# PGTN020_envelope4.net
KiCad netlist of a schematic drawn in EAGLE
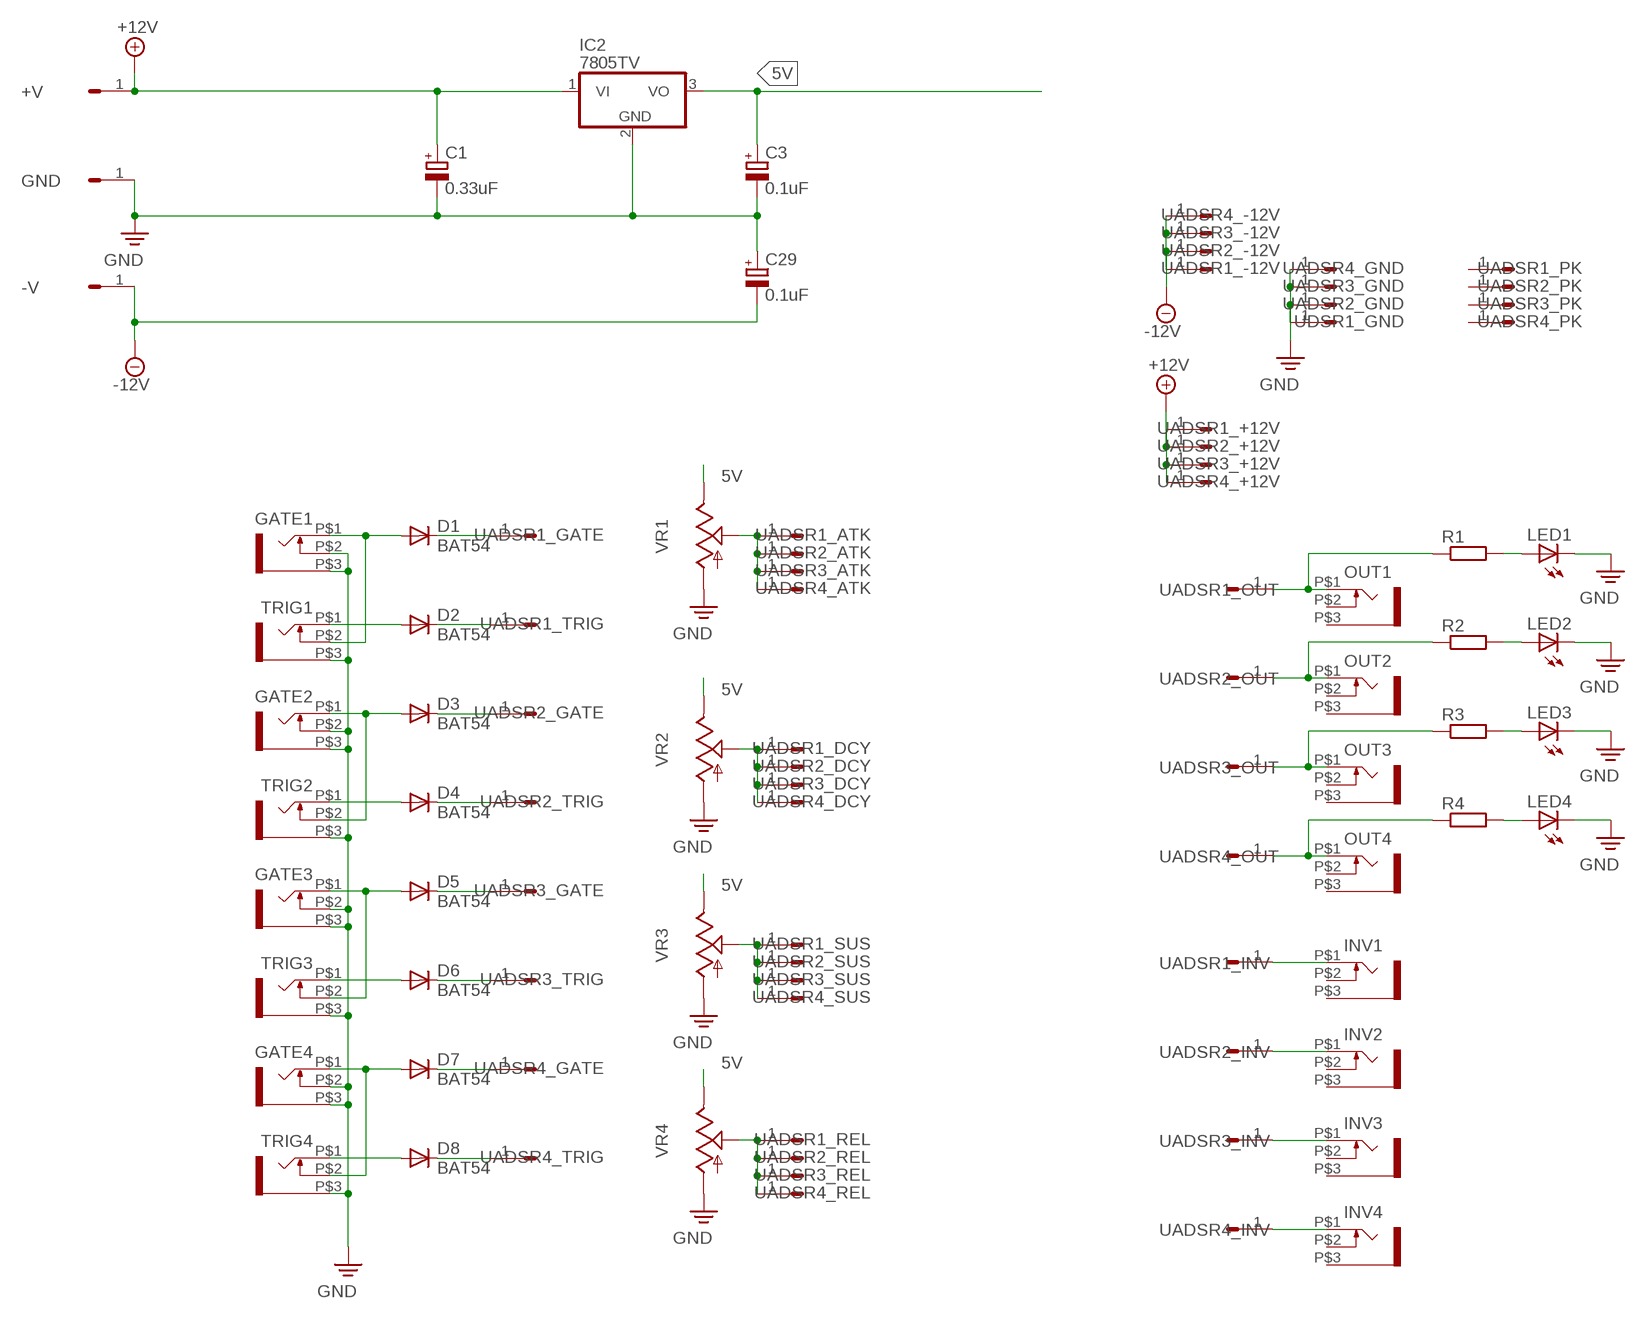
[diagram p0: schematic, sheet 1]

(export (version "E")
  (design (tool "Eeschema 10.0.6"))
  (components
    (comp (ref "+V")
      (value "HEADER/MALE/01")
      (footprint "eagle-import:HEADER_MALE_01")
      (fields (field (name "SPICEPREFIX") "X"))
      (libsource (lib "eagle-import") (part "HEADER/MALE/01"))
    )
    (comp (ref "-V")
      (value "HEADER/MALE/01")
      (footprint "eagle-import:HEADER_MALE_01")
      (fields (field (name "SPICEPREFIX") "X"))
      (libsource (lib "eagle-import") (part "HEADER/MALE/01"))
    )
    (comp (ref "C1")
      (value "0.33uF")
      (footprint "eagle-import:E2,5-6")
      (fields (field (name "SPICEPREFIX") "C"))
      (libsource (lib "eagle-import") (part "CAPACITOR/POLARIZEDE2.5-6"))
    )
    (comp (ref "C3")
      (value "0.1uF")
      (footprint "eagle-import:E2,5-6")
      (fields (field (name "SPICEPREFIX") "C"))
      (libsource (lib "eagle-import") (part "CAPACITOR/POLARIZEDE2.5-6"))
    )
    (comp (ref "C29")
      (value "0.1uF")
      (footprint "eagle-import:E2,5-6")
      (fields (field (name "SPICEPREFIX") "C"))
      (libsource (lib "eagle-import") (part "CAPACITOR/POLARIZEDE2.5-6"))
    )
    (comp (ref "D1")
      (value "BAT54")
      (footprint "eagle-import:DO35-7")
      (libsource (lib "eagle-import") (part "1N4148DO35-7"))
    )
    (comp (ref "D2")
      (value "BAT54")
      (footprint "eagle-import:DO35-7")
      (libsource (lib "eagle-import") (part "1N4148DO35-7"))
    )
    (comp (ref "D3")
      (value "BAT54")
      (footprint "eagle-import:DO35-7")
      (libsource (lib "eagle-import") (part "1N4148DO35-7"))
    )
    (comp (ref "D4")
      (value "BAT54")
      (footprint "eagle-import:DO35-7")
      (libsource (lib "eagle-import") (part "1N4148DO35-7"))
    )
    (comp (ref "D5")
      (value "BAT54")
      (footprint "eagle-import:DO35-7")
      (libsource (lib "eagle-import") (part "1N4148DO35-7"))
    )
    (comp (ref "D6")
      (value "BAT54")
      (footprint "eagle-import:DO35-7")
      (libsource (lib "eagle-import") (part "1N4148DO35-7"))
    )
    (comp (ref "D7")
      (value "BAT54")
      (footprint "eagle-import:DO35-7")
      (libsource (lib "eagle-import") (part "1N4148DO35-7"))
    )
    (comp (ref "D8")
      (value "BAT54")
      (footprint "eagle-import:DO35-7")
      (libsource (lib "eagle-import") (part "1N4148DO35-7"))
    )
    (comp (ref "GATE1")
      (value "WQP-PJ301M-12_JACK")
      (footprint "eagle-import:WQP-PJ301M-12_JACK")
      (libsource (lib "eagle-import") (part "WQP-PJ301M-12_JACK"))
    )
    (comp (ref "GATE2")
      (value "WQP-PJ301M-12_JACK")
      (footprint "eagle-import:WQP-PJ301M-12_JACK")
      (libsource (lib "eagle-import") (part "WQP-PJ301M-12_JACK"))
    )
    (comp (ref "GATE3")
      (value "WQP-PJ301M-12_JACK")
      (footprint "eagle-import:WQP-PJ301M-12_JACK")
      (libsource (lib "eagle-import") (part "WQP-PJ301M-12_JACK"))
    )
    (comp (ref "GATE4")
      (value "WQP-PJ301M-12_JACK")
      (footprint "eagle-import:WQP-PJ301M-12_JACK")
      (libsource (lib "eagle-import") (part "WQP-PJ301M-12_JACK"))
    )
    (comp (ref "GND")
      (value "HEADER/MALE/01")
      (footprint "eagle-import:HEADER_MALE_01")
      (fields (field (name "SPICEPREFIX") "X"))
      (libsource (lib "eagle-import") (part "HEADER/MALE/01"))
    )
    (comp (ref "IC2")
      (value "7805TV")
      (footprint "eagle-import:TO220V")
      (libsource (lib "eagle-import") (part "78TV05"))
    )
    (comp (ref "INV1")
      (value "WQP-PJ301M-12_JACK")
      (footprint "eagle-import:WQP-PJ301M-12_JACK")
      (libsource (lib "eagle-import") (part "WQP-PJ301M-12_JACK"))
    )
    (comp (ref "INV2")
      (value "WQP-PJ301M-12_JACK")
      (footprint "eagle-import:WQP-PJ301M-12_JACK")
      (libsource (lib "eagle-import") (part "WQP-PJ301M-12_JACK"))
    )
    (comp (ref "INV3")
      (value "WQP-PJ301M-12_JACK")
      (footprint "eagle-import:WQP-PJ301M-12_JACK")
      (libsource (lib "eagle-import") (part "WQP-PJ301M-12_JACK"))
    )
    (comp (ref "INV4")
      (value "WQP-PJ301M-12_JACK")
      (footprint "eagle-import:WQP-PJ301M-12_JACK")
      (libsource (lib "eagle-import") (part "WQP-PJ301M-12_JACK"))
    )
    (comp (ref "LED1")
      (value "LED5MM")
      (footprint "eagle-import:LED5MM")
      (libsource (lib "eagle-import") (part "LED5MM"))
    )
    (comp (ref "LED2")
      (value "LED5MM")
      (footprint "eagle-import:LED5MM")
      (libsource (lib "eagle-import") (part "LED5MM"))
    )
    (comp (ref "LED3")
      (value "LED5MM")
      (footprint "eagle-import:LED5MM")
      (libsource (lib "eagle-import") (part "LED5MM"))
    )
    (comp (ref "LED4")
      (value "LED5MM")
      (footprint "eagle-import:LED5MM")
      (libsource (lib "eagle-import") (part "LED5MM"))
    )
    (comp (ref "OUT1")
      (value "WQP-PJ301M-12_JACK")
      (footprint "eagle-import:WQP-PJ301M-12_JACK")
      (libsource (lib "eagle-import") (part "WQP-PJ301M-12_JACK"))
    )
    (comp (ref "OUT2")
      (value "WQP-PJ301M-12_JACK")
      (footprint "eagle-import:WQP-PJ301M-12_JACK")
      (libsource (lib "eagle-import") (part "WQP-PJ301M-12_JACK"))
    )
    (comp (ref "OUT3")
      (value "WQP-PJ301M-12_JACK")
      (footprint "eagle-import:WQP-PJ301M-12_JACK")
      (libsource (lib "eagle-import") (part "WQP-PJ301M-12_JACK"))
    )
    (comp (ref "OUT4")
      (value "WQP-PJ301M-12_JACK")
      (footprint "eagle-import:WQP-PJ301M-12_JACK")
      (libsource (lib "eagle-import") (part "WQP-PJ301M-12_JACK"))
    )
    (comp (ref "R1")
      (value "RESISTORRESISTOR/UPRIGHT/7.5")
      (footprint "eagle-import:RESISTOR_7.5")
      (libsource (lib "eagle-import") (part "RESISTORRESISTOR/UPRIGHT/7.5"))
    )
    (comp (ref "R2")
      (value "RESISTORRESISTOR/UPRIGHT/7.5")
      (footprint "eagle-import:RESISTOR_7.5")
      (libsource (lib "eagle-import") (part "RESISTORRESISTOR/UPRIGHT/7.5"))
    )
    (comp (ref "R3")
      (value "RESISTORRESISTOR/UPRIGHT/7.5")
      (footprint "eagle-import:RESISTOR_7.5")
      (libsource (lib "eagle-import") (part "RESISTORRESISTOR/UPRIGHT/7.5"))
    )
    (comp (ref "R4")
      (value "RESISTORRESISTOR/UPRIGHT/7.5")
      (footprint "eagle-import:RESISTOR_7.5")
      (libsource (lib "eagle-import") (part "RESISTORRESISTOR/UPRIGHT/7.5"))
    )
    (comp (ref "TRIG1")
      (value "WQP-PJ301M-12_JACK")
      (footprint "eagle-import:WQP-PJ301M-12_JACK")
      (libsource (lib "eagle-import") (part "WQP-PJ301M-12_JACK"))
    )
    (comp (ref "TRIG2")
      (value "WQP-PJ301M-12_JACK")
      (footprint "eagle-import:WQP-PJ301M-12_JACK")
      (libsource (lib "eagle-import") (part "WQP-PJ301M-12_JACK"))
    )
    (comp (ref "TRIG3")
      (value "WQP-PJ301M-12_JACK")
      (footprint "eagle-import:WQP-PJ301M-12_JACK")
      (libsource (lib "eagle-import") (part "WQP-PJ301M-12_JACK"))
    )
    (comp (ref "TRIG4")
      (value "WQP-PJ301M-12_JACK")
      (footprint "eagle-import:WQP-PJ301M-12_JACK")
      (libsource (lib "eagle-import") (part "WQP-PJ301M-12_JACK"))
    )
    (comp (ref "UADSR1_+12V")
      (value "HEADER/MALE/01")
      (footprint "eagle-import:HEADER_MALE_01")
      (fields (field (name "SPICEPREFIX") "X"))
      (libsource (lib "eagle-import") (part "HEADER/MALE/01"))
    )
    (comp (ref "UADSR1_-12V")
      (value "HEADER/MALE/01")
      (footprint "eagle-import:HEADER_MALE_01")
      (fields (field (name "SPICEPREFIX") "X"))
      (libsource (lib "eagle-import") (part "HEADER/MALE/01"))
    )
    (comp (ref "UADSR1_ATK")
      (value "HEADER/MALE/01")
      (footprint "eagle-import:HEADER_MALE_01")
      (fields (field (name "SPICEPREFIX") "X"))
      (libsource (lib "eagle-import") (part "HEADER/MALE/01"))
    )
    (comp (ref "UADSR1_DCY")
      (value "HEADER/MALE/01")
      (footprint "eagle-import:HEADER_MALE_01")
      (fields (field (name "SPICEPREFIX") "X"))
      (libsource (lib "eagle-import") (part "HEADER/MALE/01"))
    )
    (comp (ref "UADSR1_GATE")
      (value "HEADER/MALE/01")
      (footprint "eagle-import:HEADER_MALE_01")
      (fields (field (name "SPICEPREFIX") "X"))
      (libsource (lib "eagle-import") (part "HEADER/MALE/01"))
    )
    (comp (ref "UADSR1_INV")
      (value "HEADER/MALE/01")
      (footprint "eagle-import:HEADER_MALE_01")
      (fields (field (name "SPICEPREFIX") "X"))
      (libsource (lib "eagle-import") (part "HEADER/MALE/01"))
    )
    (comp (ref "UADSR1_OUT")
      (value "HEADER/MALE/01")
      (footprint "eagle-import:HEADER_MALE_01")
      (fields (field (name "SPICEPREFIX") "X"))
      (libsource (lib "eagle-import") (part "HEADER/MALE/01"))
    )
    (comp (ref "UADSR1_PK")
      (value "HEADER/MALE/01")
      (footprint "eagle-import:HEADER_MALE_01")
      (fields (field (name "SPICEPREFIX") "X"))
      (libsource (lib "eagle-import") (part "HEADER/MALE/01"))
    )
    (comp (ref "UADSR1_REL")
      (value "HEADER/MALE/01")
      (footprint "eagle-import:HEADER_MALE_01")
      (fields (field (name "SPICEPREFIX") "X"))
      (libsource (lib "eagle-import") (part "HEADER/MALE/01"))
    )
    (comp (ref "UADSR1_SUS")
      (value "HEADER/MALE/01")
      (footprint "eagle-import:HEADER_MALE_01")
      (fields (field (name "SPICEPREFIX") "X"))
      (libsource (lib "eagle-import") (part "HEADER/MALE/01"))
    )
    (comp (ref "UADSR1_TRIG")
      (value "HEADER/MALE/01")
      (footprint "eagle-import:HEADER_MALE_01")
      (fields (field (name "SPICEPREFIX") "X"))
      (libsource (lib "eagle-import") (part "HEADER/MALE/01"))
    )
    (comp (ref "UADSR2_+12V")
      (value "HEADER/MALE/01")
      (footprint "eagle-import:HEADER_MALE_01")
      (fields (field (name "SPICEPREFIX") "X"))
      (libsource (lib "eagle-import") (part "HEADER/MALE/01"))
    )
    (comp (ref "UADSR2_-12V")
      (value "HEADER/MALE/01")
      (footprint "eagle-import:HEADER_MALE_01")
      (fields (field (name "SPICEPREFIX") "X"))
      (libsource (lib "eagle-import") (part "HEADER/MALE/01"))
    )
    (comp (ref "UADSR2_ATK")
      (value "HEADER/MALE/01")
      (footprint "eagle-import:HEADER_MALE_01")
      (fields (field (name "SPICEPREFIX") "X"))
      (libsource (lib "eagle-import") (part "HEADER/MALE/01"))
    )
    (comp (ref "UADSR2_DCY")
      (value "HEADER/MALE/01")
      (footprint "eagle-import:HEADER_MALE_01")
      (fields (field (name "SPICEPREFIX") "X"))
      (libsource (lib "eagle-import") (part "HEADER/MALE/01"))
    )
    (comp (ref "UADSR2_GATE")
      (value "HEADER/MALE/01")
      (footprint "eagle-import:HEADER_MALE_01")
      (fields (field (name "SPICEPREFIX") "X"))
      (libsource (lib "eagle-import") (part "HEADER/MALE/01"))
    )
    (comp (ref "UADSR2_GND")
      (value "HEADER/MALE/01")
      (footprint "eagle-import:HEADER_MALE_01")
      (fields (field (name "SPICEPREFIX") "X"))
      (libsource (lib "eagle-import") (part "HEADER/MALE/01"))
    )
    (comp (ref "UADSR2_INV")
      (value "HEADER/MALE/01")
      (footprint "eagle-import:HEADER_MALE_01")
      (fields (field (name "SPICEPREFIX") "X"))
      (libsource (lib "eagle-import") (part "HEADER/MALE/01"))
    )
    (comp (ref "UADSR2_OUT")
      (value "HEADER/MALE/01")
      (footprint "eagle-import:HEADER_MALE_01")
      (fields (field (name "SPICEPREFIX") "X"))
      (libsource (lib "eagle-import") (part "HEADER/MALE/01"))
    )
    (comp (ref "UADSR2_PK")
      (value "HEADER/MALE/01")
      (footprint "eagle-import:HEADER_MALE_01")
      (fields (field (name "SPICEPREFIX") "X"))
      (libsource (lib "eagle-import") (part "HEADER/MALE/01"))
    )
    (comp (ref "UADSR2_REL")
      (value "HEADER/MALE/01")
      (footprint "eagle-import:HEADER_MALE_01")
      (fields (field (name "SPICEPREFIX") "X"))
      (libsource (lib "eagle-import") (part "HEADER/MALE/01"))
    )
    (comp (ref "UADSR2_SUS")
      (value "HEADER/MALE/01")
      (footprint "eagle-import:HEADER_MALE_01")
      (fields (field (name "SPICEPREFIX") "X"))
      (libsource (lib "eagle-import") (part "HEADER/MALE/01"))
    )
    (comp (ref "UADSR2_TRIG")
      (value "HEADER/MALE/01")
      (footprint "eagle-import:HEADER_MALE_01")
      (fields (field (name "SPICEPREFIX") "X"))
      (libsource (lib "eagle-import") (part "HEADER/MALE/01"))
    )
    (comp (ref "UADSR3_+12V")
      (value "HEADER/MALE/01")
      (footprint "eagle-import:HEADER_MALE_01")
      (fields (field (name "SPICEPREFIX") "X"))
      (libsource (lib "eagle-import") (part "HEADER/MALE/01"))
    )
    (comp (ref "UADSR3_-12V")
      (value "HEADER/MALE/01")
      (footprint "eagle-import:HEADER_MALE_01")
      (fields (field (name "SPICEPREFIX") "X"))
      (libsource (lib "eagle-import") (part "HEADER/MALE/01"))
    )
    (comp (ref "UADSR3_ATK")
      (value "HEADER/MALE/01")
      (footprint "eagle-import:HEADER_MALE_01")
      (fields (field (name "SPICEPREFIX") "X"))
      (libsource (lib "eagle-import") (part "HEADER/MALE/01"))
    )
    (comp (ref "UADSR3_DCY")
      (value "HEADER/MALE/01")
      (footprint "eagle-import:HEADER_MALE_01")
      (fields (field (name "SPICEPREFIX") "X"))
      (libsource (lib "eagle-import") (part "HEADER/MALE/01"))
    )
    (comp (ref "UADSR3_GATE")
      (value "HEADER/MALE/01")
      (footprint "eagle-import:HEADER_MALE_01")
      (fields (field (name "SPICEPREFIX") "X"))
      (libsource (lib "eagle-import") (part "HEADER/MALE/01"))
    )
    (comp (ref "UADSR3_GND")
      (value "HEADER/MALE/01")
      (footprint "eagle-import:HEADER_MALE_01")
      (fields (field (name "SPICEPREFIX") "X"))
      (libsource (lib "eagle-import") (part "HEADER/MALE/01"))
    )
    (comp (ref "UADSR3_INV")
      (value "HEADER/MALE/01")
      (footprint "eagle-import:HEADER_MALE_01")
      (fields (field (name "SPICEPREFIX") "X"))
      (libsource (lib "eagle-import") (part "HEADER/MALE/01"))
    )
    (comp (ref "UADSR3_OUT")
      (value "HEADER/MALE/01")
      (footprint "eagle-import:HEADER_MALE_01")
      (fields (field (name "SPICEPREFIX") "X"))
      (libsource (lib "eagle-import") (part "HEADER/MALE/01"))
    )
    (comp (ref "UADSR3_PK")
      (value "HEADER/MALE/01")
      (footprint "eagle-import:HEADER_MALE_01")
      (fields (field (name "SPICEPREFIX") "X"))
      (libsource (lib "eagle-import") (part "HEADER/MALE/01"))
    )
    (comp (ref "UADSR3_REL")
      (value "HEADER/MALE/01")
      (footprint "eagle-import:HEADER_MALE_01")
      (fields (field (name "SPICEPREFIX") "X"))
      (libsource (lib "eagle-import") (part "HEADER/MALE/01"))
    )
    (comp (ref "UADSR3_SUS")
      (value "HEADER/MALE/01")
      (footprint "eagle-import:HEADER_MALE_01")
      (fields (field (name "SPICEPREFIX") "X"))
      (libsource (lib "eagle-import") (part "HEADER/MALE/01"))
    )
    (comp (ref "UADSR3_TRIG")
      (value "HEADER/MALE/01")
      (footprint "eagle-import:HEADER_MALE_01")
      (fields (field (name "SPICEPREFIX") "X"))
      (libsource (lib "eagle-import") (part "HEADER/MALE/01"))
    )
    (comp (ref "UADSR4_+12V")
      (value "HEADER/MALE/01")
      (footprint "eagle-import:HEADER_MALE_01")
      (fields (field (name "SPICEPREFIX") "X"))
      (libsource (lib "eagle-import") (part "HEADER/MALE/01"))
    )
    (comp (ref "UADSR4_-12V")
      (value "HEADER/MALE/01")
      (footprint "eagle-import:HEADER_MALE_01")
      (fields (field (name "SPICEPREFIX") "X"))
      (libsource (lib "eagle-import") (part "HEADER/MALE/01"))
    )
    (comp (ref "UADSR4_ATK")
      (value "HEADER/MALE/01")
      (footprint "eagle-import:HEADER_MALE_01")
      (fields (field (name "SPICEPREFIX") "X"))
      (libsource (lib "eagle-import") (part "HEADER/MALE/01"))
    )
    (comp (ref "UADSR4_DCY")
      (value "HEADER/MALE/01")
      (footprint "eagle-import:HEADER_MALE_01")
      (fields (field (name "SPICEPREFIX") "X"))
      (libsource (lib "eagle-import") (part "HEADER/MALE/01"))
    )
    (comp (ref "UADSR4_GATE")
      (value "HEADER/MALE/01")
      (footprint "eagle-import:HEADER_MALE_01")
      (fields (field (name "SPICEPREFIX") "X"))
      (libsource (lib "eagle-import") (part "HEADER/MALE/01"))
    )
    (comp (ref "UADSR4_GND")
      (value "HEADER/MALE/01")
      (footprint "eagle-import:HEADER_MALE_01")
      (fields (field (name "SPICEPREFIX") "X"))
      (libsource (lib "eagle-import") (part "HEADER/MALE/01"))
    )
    (comp (ref "UADSR4_INV")
      (value "HEADER/MALE/01")
      (footprint "eagle-import:HEADER_MALE_01")
      (fields (field (name "SPICEPREFIX") "X"))
      (libsource (lib "eagle-import") (part "HEADER/MALE/01"))
    )
    (comp (ref "UADSR4_OUT")
      (value "HEADER/MALE/01")
      (footprint "eagle-import:HEADER_MALE_01")
      (fields (field (name "SPICEPREFIX") "X"))
      (libsource (lib "eagle-import") (part "HEADER/MALE/01"))
    )
    (comp (ref "UADSR4_PK")
      (value "HEADER/MALE/01")
      (footprint "eagle-import:HEADER_MALE_01")
      (fields (field (name "SPICEPREFIX") "X"))
      (libsource (lib "eagle-import") (part "HEADER/MALE/01"))
    )
    (comp (ref "UADSR4_REL")
      (value "HEADER/MALE/01")
      (footprint "eagle-import:HEADER_MALE_01")
      (fields (field (name "SPICEPREFIX") "X"))
      (libsource (lib "eagle-import") (part "HEADER/MALE/01"))
    )
    (comp (ref "UADSR4_SUS")
      (value "HEADER/MALE/01")
      (footprint "eagle-import:HEADER_MALE_01")
      (fields (field (name "SPICEPREFIX") "X"))
      (libsource (lib "eagle-import") (part "HEADER/MALE/01"))
    )
    (comp (ref "UADSR4_TRIG")
      (value "HEADER/MALE/01")
      (footprint "eagle-import:HEADER_MALE_01")
      (fields (field (name "SPICEPREFIX") "X"))
      (libsource (lib "eagle-import") (part "HEADER/MALE/01"))
    )
    (comp (ref "UDSR1_GND")
      (value "HEADER/MALE/01")
      (footprint "eagle-import:HEADER_MALE_01")
      (fields (field (name "SPICEPREFIX") "X"))
      (libsource (lib "eagle-import") (part "HEADER/MALE/01"))
    )
    (comp (ref "VR1")
      (value "9MM_SNAP-IN_POT_")
      (footprint "eagle-import:9MM_SNAP-IN_POT")
      (libsource (lib "eagle-import") (part "9MM_SNAP-IN_POT_"))
    )
    (comp (ref "VR2")
      (value "9MM_SNAP-IN_POT_")
      (footprint "eagle-import:9MM_SNAP-IN_POT")
      (libsource (lib "eagle-import") (part "9MM_SNAP-IN_POT_"))
    )
    (comp (ref "VR3")
      (value "9MM_SNAP-IN_POT_")
      (footprint "eagle-import:9MM_SNAP-IN_POT")
      (libsource (lib "eagle-import") (part "9MM_SNAP-IN_POT_"))
    )
    (comp (ref "VR4")
      (value "9MM_SNAP-IN_POT_")
      (footprint "eagle-import:9MM_SNAP-IN_POT")
      (libsource (lib "eagle-import") (part "9MM_SNAP-IN_POT_"))
    )
  )
  (nets
    (net (code "1") (name "+12V") (class "Default")
      (node (ref "+V") (pin "1") (pinfunction "3_1") (pintype "passive"))
      (node (ref "C1") (pin "+") (pinfunction "+_+") (pintype "passive"))
      (node (ref "IC2") (pin "1") (pinfunction "VI_1") (pintype "input"))
      (node (ref "UADSR1_+12V") (pin "1") (pinfunction "3_1") (pintype "passive"))
      (node (ref "UADSR2_+12V") (pin "1") (pinfunction "3_1") (pintype "passive"))
      (node (ref "UADSR3_+12V") (pin "1") (pinfunction "3_1") (pintype "passive"))
      (node (ref "UADSR4_+12V") (pin "1") (pinfunction "3_1") (pintype "passive"))
    )
    (net (code "2") (name "-12V") (class "Default")
      (node (ref "-V") (pin "1") (pinfunction "3_1") (pintype "passive"))
      (node (ref "C29") (pin "-") (pinfunction "-_-") (pintype "passive"))
      (node (ref "UADSR1_-12V") (pin "1") (pinfunction "3_1") (pintype "passive"))
      (node (ref "UADSR2_-12V") (pin "1") (pinfunction "3_1") (pintype "passive"))
      (node (ref "UADSR3_-12V") (pin "1") (pinfunction "3_1") (pintype "passive"))
      (node (ref "UADSR4_-12V") (pin "1") (pinfunction "3_1") (pintype "passive"))
    )
    (net (code "3") (name "5V") (class "Default")
      (node (ref "C3") (pin "+") (pinfunction "+_+") (pintype "passive"))
      (node (ref "IC2") (pin "3") (pinfunction "VO_3") (pintype "passive"))
      (node (ref "VR1") (pin "3") (pinfunction "E_3") (pintype "passive"))
      (node (ref "VR2") (pin "3") (pinfunction "E_3") (pintype "passive"))
      (node (ref "VR3") (pin "3") (pinfunction "E_3") (pintype "passive"))
      (node (ref "VR4") (pin "3") (pinfunction "E_3") (pintype "passive"))
    )
    (net (code "4") (name "GND") (class "Default")
      (node (ref "C1") (pin "-") (pinfunction "-_-") (pintype "passive"))
      (node (ref "C29") (pin "+") (pinfunction "+_+") (pintype "passive"))
      (node (ref "C3") (pin "-") (pinfunction "-_-") (pintype "passive"))
      (node (ref "GATE1") (pin "P$2") (pinfunction "3_P$2") (pintype "passive"))
      (node (ref "GATE1") (pin "P$3") (pinfunction "1_P$3") (pintype "passive"))
      (node (ref "GATE2") (pin "P$2") (pinfunction "3_P$2") (pintype "passive"))
      (node (ref "GATE2") (pin "P$3") (pinfunction "1_P$3") (pintype "passive"))
      (node (ref "GATE3") (pin "P$2") (pinfunction "3_P$2") (pintype "passive"))
      (node (ref "GATE3") (pin "P$3") (pinfunction "1_P$3") (pintype "passive"))
      (node (ref "GATE4") (pin "P$2") (pinfunction "3_P$2") (pintype "passive"))
      (node (ref "GATE4") (pin "P$3") (pinfunction "1_P$3") (pintype "passive"))
      (node (ref "GND") (pin "1") (pinfunction "3_1") (pintype "passive"))
      (node (ref "IC2") (pin "2") (pinfunction "GND_2") (pintype "passive"))
      (node (ref "LED1") (pin "K") (pinfunction "C_K") (pintype "passive"))
      (node (ref "LED2") (pin "K") (pinfunction "C_K") (pintype "passive"))
      (node (ref "LED3") (pin "K") (pinfunction "C_K") (pintype "passive"))
      (node (ref "LED4") (pin "K") (pinfunction "C_K") (pintype "passive"))
      (node (ref "TRIG1") (pin "P$3") (pinfunction "1_P$3") (pintype "passive"))
      (node (ref "TRIG2") (pin "P$3") (pinfunction "1_P$3") (pintype "passive"))
      (node (ref "TRIG3") (pin "P$3") (pinfunction "1_P$3") (pintype "passive"))
      (node (ref "TRIG4") (pin "P$3") (pinfunction "1_P$3") (pintype "passive"))
      (node (ref "UADSR2_GND") (pin "1") (pinfunction "3_1") (pintype "passive"))
      (node (ref "UADSR3_GND") (pin "1") (pinfunction "3_1") (pintype "passive"))
      (node (ref "UADSR4_GND") (pin "1") (pinfunction "3_1") (pintype "passive"))
      (node (ref "UDSR1_GND") (pin "1") (pinfunction "3_1") (pintype "passive"))
      (node (ref "VR1") (pin "1") (pinfunction "A_1") (pintype "passive"))
      (node (ref "VR2") (pin "1") (pinfunction "A_1") (pintype "passive"))
      (node (ref "VR3") (pin "1") (pinfunction "A_1") (pintype "passive"))
      (node (ref "VR4") (pin "1") (pinfunction "A_1") (pintype "passive"))
    )
    (net (code "5") (name "Net-(GATE1-2)") (class "Default")
      (node (ref "D1") (pin "A") (pinfunction "A_A") (pintype "passive"))
      (node (ref "GATE1") (pin "P$1") (pinfunction "2_P$1") (pintype "passive"))
      (node (ref "TRIG1") (pin "P$2") (pinfunction "3_P$2") (pintype "passive"))
    )
    (net (code "6") (name "Net-(GATE2-2)") (class "Default")
      (node (ref "D3") (pin "A") (pinfunction "A_A") (pintype "passive"))
      (node (ref "GATE2") (pin "P$1") (pinfunction "2_P$1") (pintype "passive"))
      (node (ref "TRIG2") (pin "P$2") (pinfunction "3_P$2") (pintype "passive"))
    )
    (net (code "7") (name "Net-(GATE3-2)") (class "Default")
      (node (ref "D5") (pin "A") (pinfunction "A_A") (pintype "passive"))
      (node (ref "GATE3") (pin "P$1") (pinfunction "2_P$1") (pintype "passive"))
      (node (ref "TRIG3") (pin "P$2") (pinfunction "3_P$2") (pintype "passive"))
    )
    (net (code "8") (name "Net-(GATE4-2)") (class "Default")
      (node (ref "D7") (pin "A") (pinfunction "A_A") (pintype "passive"))
      (node (ref "GATE4") (pin "P$1") (pinfunction "2_P$1") (pintype "passive"))
      (node (ref "TRIG4") (pin "P$2") (pinfunction "3_P$2") (pintype "passive"))
    )
    (net (code "9") (name "Net-(INV1-2)") (class "Default")
      (node (ref "INV1") (pin "P$1") (pinfunction "2_P$1") (pintype "passive"))
      (node (ref "UADSR1_INV") (pin "1") (pinfunction "3_1") (pintype "passive"))
    )
    (net (code "10") (name "Net-(INV2-2)") (class "Default")
      (node (ref "INV2") (pin "P$1") (pinfunction "2_P$1") (pintype "passive"))
      (node (ref "UADSR2_INV") (pin "1") (pinfunction "3_1") (pintype "passive"))
    )
    (net (code "11") (name "Net-(INV3-2)") (class "Default")
      (node (ref "INV3") (pin "P$1") (pinfunction "2_P$1") (pintype "passive"))
      (node (ref "UADSR3_INV") (pin "1") (pinfunction "3_1") (pintype "passive"))
    )
    (net (code "12") (name "Net-(INV4-2)") (class "Default")
      (node (ref "INV4") (pin "P$1") (pinfunction "2_P$1") (pintype "passive"))
      (node (ref "UADSR4_INV") (pin "1") (pinfunction "3_1") (pintype "passive"))
    )
    (net (code "13") (name "Net-(LED1-PadA)") (class "Default")
      (node (ref "LED1") (pin "A") (pinfunction "A_A") (pintype "passive"))
      (node (ref "R1") (pin "2") (pinfunction "2_2") (pintype "passive"))
    )
    (net (code "14") (name "Net-(LED2-PadA)") (class "Default")
      (node (ref "LED2") (pin "A") (pinfunction "A_A") (pintype "passive"))
      (node (ref "R2") (pin "2") (pinfunction "2_2") (pintype "passive"))
    )
    (net (code "15") (name "Net-(LED3-PadA)") (class "Default")
      (node (ref "LED3") (pin "A") (pinfunction "A_A") (pintype "passive"))
      (node (ref "R3") (pin "2") (pinfunction "2_2") (pintype "passive"))
    )
    (net (code "16") (name "Net-(LED4-PadA)") (class "Default")
      (node (ref "LED4") (pin "A") (pinfunction "A_A") (pintype "passive"))
      (node (ref "R4") (pin "2") (pinfunction "2_2") (pintype "passive"))
    )
    (net (code "17") (name "Net-(OUT1-2)") (class "Default")
      (node (ref "OUT1") (pin "P$1") (pinfunction "2_P$1") (pintype "passive"))
      (node (ref "R1") (pin "1") (pinfunction "1_1") (pintype "passive"))
      (node (ref "UADSR1_OUT") (pin "1") (pinfunction "3_1") (pintype "passive"))
    )
    (net (code "18") (name "Net-(OUT2-2)") (class "Default")
      (node (ref "OUT2") (pin "P$1") (pinfunction "2_P$1") (pintype "passive"))
      (node (ref "R2") (pin "1") (pinfunction "1_1") (pintype "passive"))
      (node (ref "UADSR2_OUT") (pin "1") (pinfunction "3_1") (pintype "passive"))
    )
    (net (code "19") (name "Net-(OUT3-2)") (class "Default")
      (node (ref "OUT3") (pin "P$1") (pinfunction "2_P$1") (pintype "passive"))
      (node (ref "R3") (pin "1") (pinfunction "1_1") (pintype "passive"))
      (node (ref "UADSR3_OUT") (pin "1") (pinfunction "3_1") (pintype "passive"))
    )
    (net (code "20") (name "Net-(OUT4-2)") (class "Default")
      (node (ref "OUT4") (pin "P$1") (pinfunction "2_P$1") (pintype "passive"))
      (node (ref "R4") (pin "1") (pinfunction "1_1") (pintype "passive"))
      (node (ref "UADSR4_OUT") (pin "1") (pinfunction "3_1") (pintype "passive"))
    )
    (net (code "21") (name "Net-(TRIG1-2)") (class "Default")
      (node (ref "D2") (pin "A") (pinfunction "A_A") (pintype "passive"))
      (node (ref "TRIG1") (pin "P$1") (pinfunction "2_P$1") (pintype "passive"))
    )
    (net (code "22") (name "Net-(TRIG2-2)") (class "Default")
      (node (ref "D4") (pin "A") (pinfunction "A_A") (pintype "passive"))
      (node (ref "TRIG2") (pin "P$1") (pinfunction "2_P$1") (pintype "passive"))
    )
    (net (code "23") (name "Net-(TRIG3-2)") (class "Default")
      (node (ref "D6") (pin "A") (pinfunction "A_A") (pintype "passive"))
      (node (ref "TRIG3") (pin "P$1") (pinfunction "2_P$1") (pintype "passive"))
    )
    (net (code "24") (name "Net-(TRIG4-2)") (class "Default")
      (node (ref "D8") (pin "A") (pinfunction "A_A") (pintype "passive"))
      (node (ref "TRIG4") (pin "P$1") (pinfunction "2_P$1") (pintype "passive"))
    )
    (net (code "25") (name "Net-(UADSR1_ATK-3)") (class "Default")
      (node (ref "UADSR1_ATK") (pin "1") (pinfunction "3_1") (pintype "passive"))
      (node (ref "UADSR2_ATK") (pin "1") (pinfunction "3_1") (pintype "passive"))
      (node (ref "UADSR3_ATK") (pin "1") (pinfunction "3_1") (pintype "passive"))
      (node (ref "UADSR4_ATK") (pin "1") (pinfunction "3_1") (pintype "passive"))
      (node (ref "VR1") (pin "2") (pinfunction "S_2") (pintype "passive"))
    )
    (net (code "26") (name "Net-(UADSR1_DCY-3)") (class "Default")
      (node (ref "UADSR1_DCY") (pin "1") (pinfunction "3_1") (pintype "passive"))
      (node (ref "UADSR2_DCY") (pin "1") (pinfunction "3_1") (pintype "passive"))
      (node (ref "UADSR3_DCY") (pin "1") (pinfunction "3_1") (pintype "passive"))
      (node (ref "UADSR4_DCY") (pin "1") (pinfunction "3_1") (pintype "passive"))
      (node (ref "VR2") (pin "2") (pinfunction "S_2") (pintype "passive"))
    )
    (net (code "27") (name "Net-(UADSR1_GATE-3)") (class "Default")
      (node (ref "D1") (pin "C") (pinfunction "C_C") (pintype "passive"))
      (node (ref "UADSR1_GATE") (pin "1") (pinfunction "3_1") (pintype "passive"))
    )
    (net (code "28") (name "Net-(UADSR1_REL-3)") (class "Default")
      (node (ref "UADSR1_REL") (pin "1") (pinfunction "3_1") (pintype "passive"))
      (node (ref "UADSR2_REL") (pin "1") (pinfunction "3_1") (pintype "passive"))
      (node (ref "UADSR3_REL") (pin "1") (pinfunction "3_1") (pintype "passive"))
      (node (ref "UADSR4_REL") (pin "1") (pinfunction "3_1") (pintype "passive"))
      (node (ref "VR4") (pin "2") (pinfunction "S_2") (pintype "passive"))
    )
    (net (code "29") (name "Net-(UADSR1_SUS-3)") (class "Default")
      (node (ref "UADSR1_SUS") (pin "1") (pinfunction "3_1") (pintype "passive"))
      (node (ref "UADSR2_SUS") (pin "1") (pinfunction "3_1") (pintype "passive"))
      (node (ref "UADSR3_SUS") (pin "1") (pinfunction "3_1") (pintype "passive"))
      (node (ref "UADSR4_SUS") (pin "1") (pinfunction "3_1") (pintype "passive"))
      (node (ref "VR3") (pin "2") (pinfunction "S_2") (pintype "passive"))
    )
    (net (code "30") (name "Net-(UADSR1_TRIG-3)") (class "Default")
      (node (ref "D2") (pin "C") (pinfunction "C_C") (pintype "passive"))
      (node (ref "UADSR1_TRIG") (pin "1") (pinfunction "3_1") (pintype "passive"))
    )
    (net (code "31") (name "Net-(UADSR2_GATE-3)") (class "Default")
      (node (ref "D3") (pin "C") (pinfunction "C_C") (pintype "passive"))
      (node (ref "UADSR2_GATE") (pin "1") (pinfunction "3_1") (pintype "passive"))
    )
    (net (code "32") (name "Net-(UADSR2_TRIG-3)") (class "Default")
      (node (ref "D4") (pin "C") (pinfunction "C_C") (pintype "passive"))
      (node (ref "UADSR2_TRIG") (pin "1") (pinfunction "3_1") (pintype "passive"))
    )
    (net (code "33") (name "Net-(UADSR3_GATE-3)") (class "Default")
      (node (ref "D5") (pin "C") (pinfunction "C_C") (pintype "passive"))
      (node (ref "UADSR3_GATE") (pin "1") (pinfunction "3_1") (pintype "passive"))
    )
    (net (code "34") (name "Net-(UADSR3_TRIG-3)") (class "Default")
      (node (ref "D6") (pin "C") (pinfunction "C_C") (pintype "passive"))
      (node (ref "UADSR3_TRIG") (pin "1") (pinfunction "3_1") (pintype "passive"))
    )
    (net (code "35") (name "Net-(UADSR4_GATE-3)") (class "Default")
      (node (ref "D7") (pin "C") (pinfunction "C_C") (pintype "passive"))
      (node (ref "UADSR4_GATE") (pin "1") (pinfunction "3_1") (pintype "passive"))
    )
    (net (code "36") (name "Net-(UADSR4_TRIG-3)") (class "Default")
      (node (ref "D8") (pin "C") (pinfunction "C_C") (pintype "passive"))
      (node (ref "UADSR4_TRIG") (pin "1") (pinfunction "3_1") (pintype "passive"))
    )
    (net (code "37") (name "unconnected-(INV1-1-PadP$3)") (class "Default")
      (node (ref "INV1") (pin "P$3") (pinfunction "1_P$3") (pintype "passive"))
    )
    (net (code "38") (name "unconnected-(INV1-3-PadP$2)") (class "Default")
      (node (ref "INV1") (pin "P$2") (pinfunction "3_P$2") (pintype "passive"))
    )
    (net (code "39") (name "unconnected-(INV2-1-PadP$3)") (class "Default")
      (node (ref "INV2") (pin "P$3") (pinfunction "1_P$3") (pintype "passive"))
    )
    (net (code "40") (name "unconnected-(INV2-3-PadP$2)") (class "Default")
      (node (ref "INV2") (pin "P$2") (pinfunction "3_P$2") (pintype "passive"))
    )
    (net (code "41") (name "unconnected-(INV3-1-PadP$3)") (class "Default")
      (node (ref "INV3") (pin "P$3") (pinfunction "1_P$3") (pintype "passive"))
    )
    (net (code "42") (name "unconnected-(INV3-3-PadP$2)") (class "Default")
      (node (ref "INV3") (pin "P$2") (pinfunction "3_P$2") (pintype "passive"))
    )
    (net (code "43") (name "unconnected-(INV4-1-PadP$3)") (class "Default")
      (node (ref "INV4") (pin "P$3") (pinfunction "1_P$3") (pintype "passive"))
    )
    (net (code "44") (name "unconnected-(INV4-3-PadP$2)") (class "Default")
      (node (ref "INV4") (pin "P$2") (pinfunction "3_P$2") (pintype "passive"))
    )
    (net (code "45") (name "unconnected-(OUT1-1-PadP$3)") (class "Default")
      (node (ref "OUT1") (pin "P$3") (pinfunction "1_P$3") (pintype "passive"))
    )
    (net (code "46") (name "unconnected-(OUT1-3-PadP$2)") (class "Default")
      (node (ref "OUT1") (pin "P$2") (pinfunction "3_P$2") (pintype "passive"))
    )
    (net (code "47") (name "unconnected-(OUT2-1-PadP$3)") (class "Default")
      (node (ref "OUT2") (pin "P$3") (pinfunction "1_P$3") (pintype "passive"))
    )
    (net (code "48") (name "unconnected-(OUT2-3-PadP$2)") (class "Default")
      (node (ref "OUT2") (pin "P$2") (pinfunction "3_P$2") (pintype "passive"))
    )
    (net (code "49") (name "unconnected-(OUT3-1-PadP$3)") (class "Default")
      (node (ref "OUT3") (pin "P$3") (pinfunction "1_P$3") (pintype "passive"))
    )
    (net (code "50") (name "unconnected-(OUT3-3-PadP$2)") (class "Default")
      (node (ref "OUT3") (pin "P$2") (pinfunction "3_P$2") (pintype "passive"))
    )
    (net (code "51") (name "unconnected-(OUT4-1-PadP$3)") (class "Default")
      (node (ref "OUT4") (pin "P$3") (pinfunction "1_P$3") (pintype "passive"))
    )
    (net (code "52") (name "unconnected-(OUT4-3-PadP$2)") (class "Default")
      (node (ref "OUT4") (pin "P$2") (pinfunction "3_P$2") (pintype "passive"))
    )
    (net (code "53") (name "unconnected-(UADSR1_PK-3-Pad1)") (class "Default")
      (node (ref "UADSR1_PK") (pin "1") (pinfunction "3_1") (pintype "passive"))
    )
    (net (code "54") (name "unconnected-(UADSR2_PK-3-Pad1)") (class "Default")
      (node (ref "UADSR2_PK") (pin "1") (pinfunction "3_1") (pintype "passive"))
    )
    (net (code "55") (name "unconnected-(UADSR3_PK-3-Pad1)") (class "Default")
      (node (ref "UADSR3_PK") (pin "1") (pinfunction "3_1") (pintype "passive"))
    )
    (net (code "56") (name "unconnected-(UADSR4_PK-3-Pad1)") (class "Default")
      (node (ref "UADSR4_PK") (pin "1") (pinfunction "3_1") (pintype "passive"))
    )
  )
)
